# Sheet4.net
KiCad netlist of a schematic drawn in Altium Designer
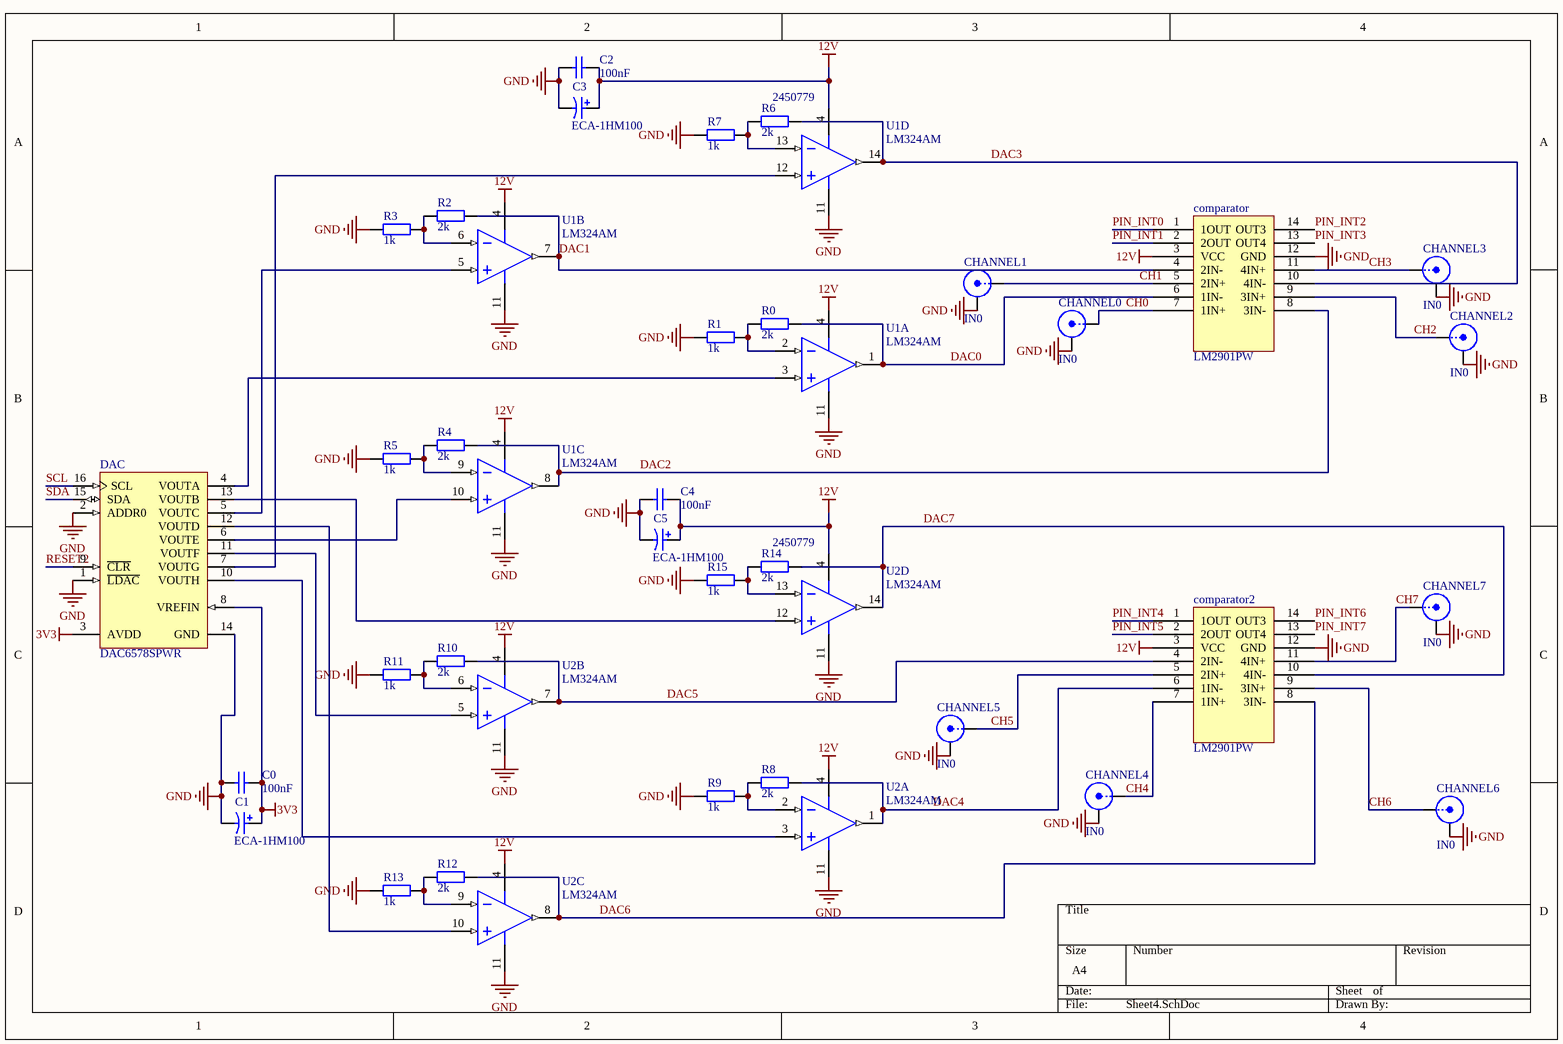
[diagram p0: Sheet4.SchDoc]

(export (version "E")
  (design (tool "Eeschema 10.0.6"))
  (components
    (comp (ref "C0")
      (value "100nF")
      (footprint "C0805")
      (description "Capacitor Cer 50V 0805 Vishay X7R")
      (libsource (lib "capacitors") (part "Ceramic 100nF/50V"))
    )
    (comp (ref "C1")
      (value "ECA-1HM100")
      (footprint "CAPPR55-200-1100X500X1200")
      (description "Aluminum Electrolytic Capacitor, 10 uF, +/- 20%, 50 V, -40 to 85 degC, 2-Pin THD, RoHS, Bulk")
      (libsource (lib "Altium Content Vault") (part "CMP-1665-00038-1"))
    )
    (comp (ref "C2")
      (value "100nF")
      (footprint "C0805")
      (description "Capacitor Cer 50V 0805 Vishay X7R")
      (libsource (lib "capacitors") (part "Ceramic 100nF/50V"))
    )
    (comp (ref "C3")
      (value "ECA-1HM100")
      (footprint "CAPPR55-200-1100X500X1200")
      (description "Aluminum Electrolytic Capacitor, 10 uF, +/- 20%, 50 V, -40 to 85 degC, 2-Pin THD, RoHS, Bulk")
      (libsource (lib "Altium Content Vault") (part "CMP-1665-00038-1"))
    )
    (comp (ref "C4")
      (value "100nF")
      (footprint "C0805")
      (description "Capacitor Cer 50V 0805 Vishay X7R")
      (libsource (lib "capacitors") (part "Ceramic 100nF/50V"))
    )
    (comp (ref "C5")
      (value "ECA-1HM100")
      (footprint "CAPPR55-200-1100X500X1200")
      (description "Aluminum Electrolytic Capacitor, 10 uF, +/- 20%, 50 V, -40 to 85 degC, 2-Pin THD, RoHS, Bulk")
      (libsource (lib "Altium Content Vault") (part "CMP-1665-00038-1"))
    )
    (comp (ref "CHANNEL0")
      (value "IN0")
      (footprint "connectors:SMB")
      (description "SMB Straight Connector")
      (fields (field (name "PUBLISHER") "Altium Limited"))
      (libsource (lib "connectors") (part "SMB"))
    )
    (comp (ref "CHANNEL1")
      (value "IN0")
      (footprint "connectors:SMB")
      (description "SMB Straight Connector")
      (fields (field (name "PUBLISHER") "Altium Limited"))
      (libsource (lib "connectors") (part "SMB"))
    )
    (comp (ref "CHANNEL2")
      (value "IN0")
      (footprint "connectors:SMB")
      (description "SMB Straight Connector")
      (fields (field (name "PUBLISHER") "Altium Limited"))
      (libsource (lib "connectors") (part "SMB"))
    )
    (comp (ref "CHANNEL3")
      (value "IN0")
      (footprint "connectors:SMB")
      (description "SMB Straight Connector")
      (fields (field (name "PUBLISHER") "Altium Limited"))
      (libsource (lib "connectors") (part "SMB"))
    )
    (comp (ref "CHANNEL4")
      (value "IN0")
      (footprint "connectors:SMB")
      (description "SMB Straight Connector")
      (fields (field (name "PUBLISHER") "Altium Limited"))
      (libsource (lib "connectors") (part "SMB"))
    )
    (comp (ref "CHANNEL5")
      (value "IN0")
      (footprint "connectors:SMB")
      (description "SMB Straight Connector")
      (fields (field (name "PUBLISHER") "Altium Limited"))
      (libsource (lib "connectors") (part "SMB"))
    )
    (comp (ref "CHANNEL6")
      (value "IN0")
      (footprint "connectors:SMB")
      (description "SMB Straight Connector")
      (fields (field (name "PUBLISHER") "Altium Limited"))
      (libsource (lib "connectors") (part "SMB"))
    )
    (comp (ref "CHANNEL7")
      (value "IN0")
      (footprint "connectors:SMB")
      (description "SMB Straight Connector")
      (fields (field (name "PUBLISHER") "Altium Limited"))
      (libsource (lib "connectors") (part "SMB"))
    )
    (comp (ref "comparator")
      (value "LM2901PW")
      (footprint "TSSOP-14")
      (libsource (lib "schlib") (part "LM2901PW"))
    )
    (comp (ref "comparator2")
      (value "LM2901PW")
      (footprint "TSSOP-14")
      (libsource (lib "schlib") (part "LM2901PW"))
    )
    (comp (ref "DAC")
      (value "DAC6578SPWR")
      (footprint "TI-PW16_N")
      (fields (field (name "MANUFACTURER") "Texas Instruments"))
      (libsource (lib "Altium Content Vault") (part "CMP-0004-01130-1"))
    )
    (comp (ref "R0")
      (value "2k")
      (footprint "6-0805_N")
      (description "Resistor")
      (fields (field (name "Comment") "1k-0W25-0805") (field (name "PUBLISHER") "Altium Limited"))
      (libsource (lib "resistors_0805") (part "1k-0W25-0805"))
    )
    (comp (ref "R1")
      (value "1k")
      (footprint "6-0805_N")
      (description "Resistor")
      (fields (field (name "Comment") "1k-0W25-0805") (field (name "PUBLISHER") "Altium Limited"))
      (libsource (lib "resistors_0805") (part "1k-0W25-0805"))
    )
    (comp (ref "R2")
      (value "2k")
      (footprint "6-0805_N")
      (description "Resistor")
      (fields (field (name "Comment") "1k-0W25-0805") (field (name "PUBLISHER") "Altium Limited"))
      (libsource (lib "resistors_0805") (part "1k-0W25-0805"))
    )
    (comp (ref "R3")
      (value "1k")
      (footprint "6-0805_N")
      (description "Resistor")
      (fields (field (name "Comment") "1k-0W25-0805") (field (name "PUBLISHER") "Altium Limited"))
      (libsource (lib "resistors_0805") (part "1k-0W25-0805"))
    )
    (comp (ref "R4")
      (value "2k")
      (footprint "6-0805_N")
      (description "Resistor")
      (fields (field (name "Comment") "1k-0W25-0805") (field (name "PUBLISHER") "Altium Limited"))
      (libsource (lib "resistors_0805") (part "1k-0W25-0805"))
    )
    (comp (ref "R5")
      (value "1k")
      (footprint "6-0805_N")
      (description "Resistor")
      (fields (field (name "Comment") "1k-0W25-0805") (field (name "PUBLISHER") "Altium Limited"))
      (libsource (lib "resistors_0805") (part "1k-0W25-0805"))
    )
    (comp (ref "R6")
      (value "2k")
      (footprint "6-0805_N")
      (description "Resistor")
      (fields (field (name "Comment") "1k-0W25-0805") (field (name "PUBLISHER") "Altium Limited"))
      (libsource (lib "resistors_0805") (part "1k-0W25-0805"))
    )
    (comp (ref "R7")
      (value "1k")
      (footprint "6-0805_N")
      (description "Resistor")
      (fields (field (name "Comment") "1k-0W25-0805") (field (name "PUBLISHER") "Altium Limited"))
      (libsource (lib "resistors_0805") (part "1k-0W25-0805"))
    )
    (comp (ref "R8")
      (value "2k")
      (footprint "6-0805_N")
      (description "Resistor")
      (fields (field (name "Comment") "1k-0W25-0805") (field (name "PUBLISHER") "Altium Limited"))
      (libsource (lib "resistors_0805") (part "1k-0W25-0805"))
    )
    (comp (ref "R9")
      (value "1k")
      (footprint "6-0805_N")
      (description "Resistor")
      (fields (field (name "Comment") "1k-0W25-0805") (field (name "PUBLISHER") "Altium Limited"))
      (libsource (lib "resistors_0805") (part "1k-0W25-0805"))
    )
    (comp (ref "R10")
      (value "2k")
      (footprint "6-0805_N")
      (description "Resistor")
      (fields (field (name "Comment") "1k-0W25-0805") (field (name "PUBLISHER") "Altium Limited"))
      (libsource (lib "resistors_0805") (part "1k-0W25-0805"))
    )
    (comp (ref "R11")
      (value "1k")
      (footprint "6-0805_N")
      (description "Resistor")
      (fields (field (name "Comment") "1k-0W25-0805") (field (name "PUBLISHER") "Altium Limited"))
      (libsource (lib "resistors_0805") (part "1k-0W25-0805"))
    )
    (comp (ref "R12")
      (value "2k")
      (footprint "6-0805_N")
      (description "Resistor")
      (fields (field (name "Comment") "1k-0W25-0805") (field (name "PUBLISHER") "Altium Limited"))
      (libsource (lib "resistors_0805") (part "1k-0W25-0805"))
    )
    (comp (ref "R13")
      (value "1k")
      (footprint "6-0805_N")
      (description "Resistor")
      (fields (field (name "Comment") "1k-0W25-0805") (field (name "PUBLISHER") "Altium Limited"))
      (libsource (lib "resistors_0805") (part "1k-0W25-0805"))
    )
    (comp (ref "R14")
      (value "2k")
      (footprint "6-0805_N")
      (description "Resistor")
      (fields (field (name "Comment") "1k-0W25-0805") (field (name "PUBLISHER") "Altium Limited"))
      (libsource (lib "resistors_0805") (part "1k-0W25-0805"))
    )
    (comp (ref "R15")
      (value "1k")
      (footprint "6-0805_N")
      (description "Resistor")
      (fields (field (name "Comment") "1k-0W25-0805") (field (name "PUBLISHER") "Altium Limited"))
      (libsource (lib "resistors_0805") (part "1k-0W25-0805"))
    )
    (comp (ref "U1")
      (value "LM324AM")
      (footprint "D0014A_N")
      (description "Low Power Quad Operational Amplifier, 14-pin Narrow SOIC")
      (fields
        (field (name "MANUFACTURER") "Texas Instruments")
        (field (name "SUPPLIER PART NUMBER 1") "2450779")
      )
      (libsource (lib "Altium Content Vault") (part "CMP-0055-00794-3"))
    )
    (comp (ref "U2")
      (value "LM324AM")
      (footprint "D0014A_N")
      (description "Low Power Quad Operational Amplifier, 14-pin Narrow SOIC")
      (fields
        (field (name "MANUFACTURER") "Texas Instruments")
        (field (name "SUPPLIER PART NUMBER 1") "2450779")
      )
      (libsource (lib "Altium Content Vault") (part "CMP-0055-00794-3"))
    )
  )
  (nets
    (net (code "1") (name "/CH0") (class "Default")
      (node (ref "CHANNEL0") (pin "1") (pinfunction "X_1") (pintype "passive"))
      (node (ref "comparator") (pin "7") (pinfunction "1IN+_7") (pintype "passive"))
    )
    (net (code "2") (name "/CH1") (class "Default")
      (node (ref "CHANNEL1") (pin "1") (pinfunction "X_1") (pintype "passive"))
      (node (ref "comparator") (pin "5") (pinfunction "2IN+_5") (pintype "passive"))
    )
    (net (code "3") (name "/CH2") (class "Default")
      (node (ref "CHANNEL2") (pin "1") (pinfunction "X_1") (pintype "passive"))
      (node (ref "comparator") (pin "9") (pinfunction "3IN+_9") (pintype "passive"))
    )
    (net (code "4") (name "/CH3") (class "Default")
      (node (ref "CHANNEL3") (pin "1") (pinfunction "X_1") (pintype "passive"))
      (node (ref "comparator") (pin "11") (pinfunction "4IN+_11") (pintype "passive"))
    )
    (net (code "5") (name "/CH4") (class "Default")
      (node (ref "CHANNEL4") (pin "1") (pinfunction "X_1") (pintype "passive"))
      (node (ref "comparator2") (pin "7") (pinfunction "1IN+_7") (pintype "passive"))
    )
    (net (code "6") (name "/CH5") (class "Default")
      (node (ref "CHANNEL5") (pin "1") (pinfunction "X_1") (pintype "passive"))
      (node (ref "comparator2") (pin "5") (pinfunction "2IN+_5") (pintype "passive"))
    )
    (net (code "7") (name "/CH6") (class "Default")
      (node (ref "CHANNEL6") (pin "1") (pinfunction "X_1") (pintype "passive"))
      (node (ref "comparator2") (pin "9") (pinfunction "3IN+_9") (pintype "passive"))
    )
    (net (code "8") (name "/CH7") (class "Default")
      (node (ref "CHANNEL7") (pin "1") (pinfunction "X_1") (pintype "passive"))
      (node (ref "comparator2") (pin "11") (pinfunction "4IN+_11") (pintype "passive"))
    )
    (net (code "9") (name "/DAC0") (class "Default")
      (node (ref "R0") (pin "2") (pinfunction "2_2") (pintype "passive"))
      (node (ref "U1") (pin "1") (pinfunction "OUT1_1") (pintype "output"))
      (node (ref "comparator") (pin "6") (pinfunction "1IN-_6") (pintype "passive"))
    )
    (net (code "10") (name "/DAC1") (class "Default")
      (node (ref "R2") (pin "2") (pinfunction "2_2") (pintype "passive"))
      (node (ref "U1") (pin "7") (pinfunction "OUT2_7") (pintype "output"))
      (node (ref "comparator") (pin "4") (pinfunction "2IN-_4") (pintype "passive"))
    )
    (net (code "11") (name "/DAC2") (class "Default")
      (node (ref "R4") (pin "2") (pinfunction "2_2") (pintype "passive"))
      (node (ref "U1") (pin "8") (pinfunction "OUT3_8") (pintype "output"))
      (node (ref "comparator") (pin "8") (pinfunction "3IN-_8") (pintype "passive"))
    )
    (net (code "12") (name "/DAC3") (class "Default")
      (node (ref "R6") (pin "2") (pinfunction "2_2") (pintype "passive"))
      (node (ref "U1") (pin "14") (pinfunction "OUT4_14") (pintype "output"))
      (node (ref "comparator") (pin "10") (pinfunction "4IN-_10") (pintype "passive"))
    )
    (net (code "13") (name "/DAC4") (class "Default")
      (node (ref "R8") (pin "2") (pinfunction "2_2") (pintype "passive"))
      (node (ref "U2") (pin "1") (pinfunction "OUT1_1") (pintype "output"))
      (node (ref "comparator2") (pin "6") (pinfunction "1IN-_6") (pintype "passive"))
    )
    (net (code "14") (name "/DAC5") (class "Default")
      (node (ref "R10") (pin "2") (pinfunction "2_2") (pintype "passive"))
      (node (ref "U2") (pin "7") (pinfunction "OUT2_7") (pintype "output"))
      (node (ref "comparator2") (pin "4") (pinfunction "2IN-_4") (pintype "passive"))
    )
    (net (code "15") (name "/DAC6") (class "Default")
      (node (ref "R12") (pin "2") (pinfunction "2_2") (pintype "passive"))
      (node (ref "U2") (pin "8") (pinfunction "OUT3_8") (pintype "output"))
      (node (ref "comparator2") (pin "8") (pinfunction "3IN-_8") (pintype "passive"))
    )
    (net (code "16") (name "/DAC7") (class "Default")
      (node (ref "R14") (pin "2") (pinfunction "2_2") (pintype "passive"))
      (node (ref "U2") (pin "14") (pinfunction "OUT4_14") (pintype "output"))
      (node (ref "comparator2") (pin "10") (pinfunction "4IN-_10") (pintype "passive"))
    )
    (net (code "17") (name "/PIN_INT0") (class "Default")
      (node (ref "comparator") (pin "1") (pinfunction "1OUT_1") (pintype "passive"))
    )
    (net (code "18") (name "/PIN_INT1") (class "Default")
      (node (ref "comparator") (pin "2") (pinfunction "2OUT_2") (pintype "passive"))
    )
    (net (code "19") (name "/PIN_INT2") (class "Default")
      (node (ref "comparator") (pin "14") (pinfunction "OUT3_14") (pintype "passive"))
    )
    (net (code "20") (name "/PIN_INT3") (class "Default")
      (node (ref "comparator") (pin "13") (pinfunction "OUT4_13") (pintype "passive"))
    )
    (net (code "21") (name "/PIN_INT4") (class "Default")
      (node (ref "comparator2") (pin "1") (pinfunction "1OUT_1") (pintype "passive"))
    )
    (net (code "22") (name "/PIN_INT5") (class "Default")
      (node (ref "comparator2") (pin "2") (pinfunction "2OUT_2") (pintype "passive"))
    )
    (net (code "23") (name "/PIN_INT6") (class "Default")
      (node (ref "comparator2") (pin "14") (pinfunction "OUT3_14") (pintype "passive"))
    )
    (net (code "24") (name "/PIN_INT7") (class "Default")
      (node (ref "comparator2") (pin "13") (pinfunction "OUT4_13") (pintype "passive"))
    )
    (net (code "25") (name "/RESET2") (class "Default")
      (node (ref "DAC") (pin "9") (pinfunction "~{CLR}_9") (pintype "input"))
    )
    (net (code "26") (name "/SCL") (class "Default")
      (node (ref "DAC") (pin "16") (pinfunction "SCL_16") (pintype "input"))
    )
    (net (code "27") (name "/SDA") (class "Default")
      (node (ref "DAC") (pin "15") (pinfunction "SDA_15") (pintype "bidirectional"))
    )
    (net (code "28") (name "3V3") (class "Default")
      (node (ref "C0") (pin "2") (pinfunction "2_2") (pintype "passive"))
      (node (ref "C1") (pin "1") (pinfunction "1_1") (pintype "passive"))
      (node (ref "DAC") (pin "3") (pinfunction "AVDD_3") (pintype "power_in"))
      (node (ref "DAC") (pin "8") (pinfunction "VREFIN_8") (pintype "input"))
    )
    (net (code "29") (name "12V") (class "Default")
      (node (ref "C2") (pin "2") (pinfunction "2_2") (pintype "passive"))
      (node (ref "C3") (pin "1") (pinfunction "1_1") (pintype "passive"))
      (node (ref "C4") (pin "2") (pinfunction "2_2") (pintype "passive"))
      (node (ref "C5") (pin "1") (pinfunction "1_1") (pintype "passive"))
      (node (ref "U1") (pin "4") (pinfunction "V+_4") (pintype "power_in"))
      (node (ref "U2") (pin "4") (pinfunction "V+_4") (pintype "power_in"))
      (node (ref "comparator") (pin "3") (pinfunction "VCC_3") (pintype "passive"))
      (node (ref "comparator2") (pin "3") (pinfunction "VCC_3") (pintype "passive"))
    )
    (net (code "30") (name "GND") (class "Default")
      (node (ref "C0") (pin "1") (pinfunction "1_1") (pintype "passive"))
      (node (ref "C1") (pin "2") (pinfunction "2_2") (pintype "passive"))
      (node (ref "C2") (pin "1") (pinfunction "1_1") (pintype "passive"))
      (node (ref "C3") (pin "2") (pinfunction "2_2") (pintype "passive"))
      (node (ref "C4") (pin "1") (pinfunction "1_1") (pintype "passive"))
      (node (ref "C5") (pin "2") (pinfunction "2_2") (pintype "passive"))
      (node (ref "CHANNEL0") (pin "2") (pinfunction "Y_2") (pintype "passive"))
      (node (ref "CHANNEL1") (pin "2") (pinfunction "Y_2") (pintype "passive"))
      (node (ref "CHANNEL2") (pin "2") (pinfunction "Y_2") (pintype "passive"))
      (node (ref "CHANNEL3") (pin "2") (pinfunction "Y_2") (pintype "passive"))
      (node (ref "CHANNEL4") (pin "2") (pinfunction "Y_2") (pintype "passive"))
      (node (ref "CHANNEL5") (pin "2") (pinfunction "Y_2") (pintype "passive"))
      (node (ref "CHANNEL6") (pin "2") (pinfunction "Y_2") (pintype "passive"))
      (node (ref "CHANNEL7") (pin "2") (pinfunction "Y_2") (pintype "passive"))
      (node (ref "DAC") (pin "1") (pinfunction "~{LDAC}_1") (pintype "input"))
      (node (ref "DAC") (pin "14") (pinfunction "GND_14") (pintype "power_in"))
      (node (ref "DAC") (pin "2") (pinfunction "ADDR0_2") (pintype "input"))
      (node (ref "R1") (pin "1") (pinfunction "1_1") (pintype "passive"))
      (node (ref "R11") (pin "1") (pinfunction "1_1") (pintype "passive"))
      (node (ref "R13") (pin "1") (pinfunction "1_1") (pintype "passive"))
      (node (ref "R15") (pin "1") (pinfunction "1_1") (pintype "passive"))
      (node (ref "R3") (pin "1") (pinfunction "1_1") (pintype "passive"))
      (node (ref "R5") (pin "1") (pinfunction "1_1") (pintype "passive"))
      (node (ref "R7") (pin "1") (pinfunction "1_1") (pintype "passive"))
      (node (ref "R9") (pin "1") (pinfunction "1_1") (pintype "passive"))
      (node (ref "U1") (pin "11") (pinfunction "GND_11") (pintype "power_in"))
      (node (ref "U2") (pin "11") (pinfunction "GND_11") (pintype "power_in"))
      (node (ref "comparator") (pin "12") (pinfunction "GND_12") (pintype "passive"))
      (node (ref "comparator2") (pin "12") (pinfunction "GND_12") (pintype "passive"))
    )
    (net (code "31") (name "Net-(DAC-VOUTA)") (class "Default")
      (node (ref "DAC") (pin "4") (pinfunction "VOUTA_4") (pintype "tri_state"))
      (node (ref "U1") (pin "3") (pinfunction "IN1+_3") (pintype "input"))
    )
    (net (code "32") (name "Net-(DAC-VOUTB)") (class "Default")
      (node (ref "DAC") (pin "13") (pinfunction "VOUTB_13") (pintype "tri_state"))
      (node (ref "U2") (pin "12") (pinfunction "IN4+_12") (pintype "input"))
    )
    (net (code "33") (name "Net-(DAC-VOUTC)") (class "Default")
      (node (ref "DAC") (pin "5") (pinfunction "VOUTC_5") (pintype "tri_state"))
      (node (ref "U1") (pin "5") (pinfunction "IN2+_5") (pintype "input"))
    )
    (net (code "34") (name "Net-(DAC-VOUTD)") (class "Default")
      (node (ref "DAC") (pin "12") (pinfunction "VOUTD_12") (pintype "tri_state"))
      (node (ref "U2") (pin "10") (pinfunction "IN3+_10") (pintype "input"))
    )
    (net (code "35") (name "Net-(DAC-VOUTE)") (class "Default")
      (node (ref "DAC") (pin "6") (pinfunction "VOUTE_6") (pintype "tri_state"))
      (node (ref "U1") (pin "10") (pinfunction "IN3+_10") (pintype "input"))
    )
    (net (code "36") (name "Net-(DAC-VOUTF)") (class "Default")
      (node (ref "DAC") (pin "11") (pinfunction "VOUTF_11") (pintype "tri_state"))
      (node (ref "U2") (pin "5") (pinfunction "IN2+_5") (pintype "input"))
    )
    (net (code "37") (name "Net-(DAC-VOUTG)") (class "Default")
      (node (ref "DAC") (pin "7") (pinfunction "VOUTG_7") (pintype "tri_state"))
      (node (ref "U1") (pin "12") (pinfunction "IN4+_12") (pintype "input"))
    )
    (net (code "38") (name "Net-(DAC-VOUTH)") (class "Default")
      (node (ref "DAC") (pin "10") (pinfunction "VOUTH_10") (pintype "tri_state"))
      (node (ref "U2") (pin "3") (pinfunction "IN1+_3") (pintype "input"))
    )
    (net (code "39") (name "Net-(U1A-IN1-)") (class "Default")
      (node (ref "R0") (pin "1") (pinfunction "1_1") (pintype "passive"))
      (node (ref "R1") (pin "2") (pinfunction "2_2") (pintype "passive"))
      (node (ref "U1") (pin "2") (pinfunction "IN1-_2") (pintype "input"))
    )
    (net (code "40") (name "Net-(U1B-IN2-)") (class "Default")
      (node (ref "R2") (pin "1") (pinfunction "1_1") (pintype "passive"))
      (node (ref "R3") (pin "2") (pinfunction "2_2") (pintype "passive"))
      (node (ref "U1") (pin "6") (pinfunction "IN2-_6") (pintype "input"))
    )
    (net (code "41") (name "Net-(U1C-IN3-)") (class "Default")
      (node (ref "R4") (pin "1") (pinfunction "1_1") (pintype "passive"))
      (node (ref "R5") (pin "2") (pinfunction "2_2") (pintype "passive"))
      (node (ref "U1") (pin "9") (pinfunction "IN3-_9") (pintype "input"))
    )
    (net (code "42") (name "Net-(U1D-IN4-)") (class "Default")
      (node (ref "R6") (pin "1") (pinfunction "1_1") (pintype "passive"))
      (node (ref "R7") (pin "2") (pinfunction "2_2") (pintype "passive"))
      (node (ref "U1") (pin "13") (pinfunction "IN4-_13") (pintype "input"))
    )
    (net (code "43") (name "Net-(U2A-IN1-)") (class "Default")
      (node (ref "R8") (pin "1") (pinfunction "1_1") (pintype "passive"))
      (node (ref "R9") (pin "2") (pinfunction "2_2") (pintype "passive"))
      (node (ref "U2") (pin "2") (pinfunction "IN1-_2") (pintype "input"))
    )
    (net (code "44") (name "Net-(U2B-IN2-)") (class "Default")
      (node (ref "R10") (pin "1") (pinfunction "1_1") (pintype "passive"))
      (node (ref "R11") (pin "2") (pinfunction "2_2") (pintype "passive"))
      (node (ref "U2") (pin "6") (pinfunction "IN2-_6") (pintype "input"))
    )
    (net (code "45") (name "Net-(U2C-IN3-)") (class "Default")
      (node (ref "R12") (pin "1") (pinfunction "1_1") (pintype "passive"))
      (node (ref "R13") (pin "2") (pinfunction "2_2") (pintype "passive"))
      (node (ref "U2") (pin "9") (pinfunction "IN3-_9") (pintype "input"))
    )
    (net (code "46") (name "Net-(U2D-IN4-)") (class "Default")
      (node (ref "R14") (pin "1") (pinfunction "1_1") (pintype "passive"))
      (node (ref "R15") (pin "2") (pinfunction "2_2") (pintype "passive"))
      (node (ref "U2") (pin "13") (pinfunction "IN4-_13") (pintype "input"))
    )
  )
)
